# ULED.net
KiCad netlist of a schematic drawn in Altium Designer
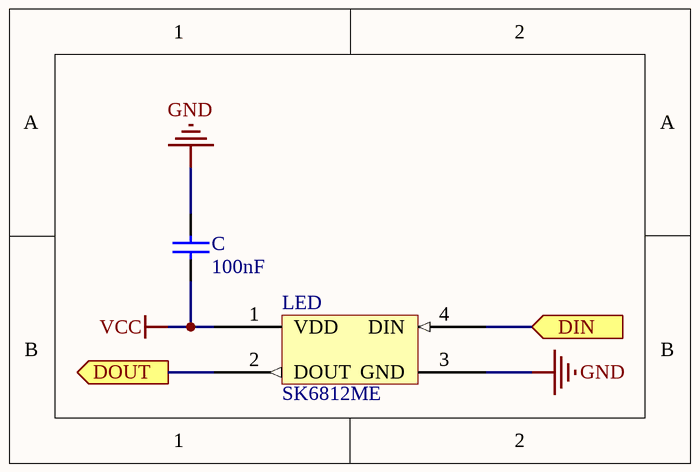
[diagram p0: ULED.SchDoc]

(export (version "E")
  (design (tool "Eeschema 10.0.6"))
  (components
    (comp (ref "C")
      (value "100nF")
      (footprint "CAPC1005X55X30LL05T10")
      (fields (field (name "MANUFACTURER") "Kemet") (field (name "PART NUMBER") "C0402C104K4RACTU"))
      (libsource (lib "Altium Content Vault") (part "CAP"))
    )
    (comp (ref "LED")
      (value "SK6812ME")
      (footprint "SK6812ME")
      (description "Individually Adressable SK6812 Mini-E 3528 LED")
      (libsource (lib "Skayboard") (part "SK6812"))
    )
  )
  (nets
    (net (code "1") (name "/DIN") (class "Default")
      (node (ref "LED") (pin "4") (pinfunction "DIN_4") (pintype "input"))
    )
    (net (code "2") (name "/DOUT") (class "Default")
      (node (ref "LED") (pin "2") (pinfunction "DOUT_2") (pintype "output"))
    )
    (net (code "3") (name "GND") (class "Default")
      (node (ref "C") (pin "2") (pinfunction "2_2") (pintype "passive"))
      (node (ref "LED") (pin "3") (pinfunction "GND_3") (pintype "power_in"))
    )
    (net (code "4") (name "VCC") (class "Default")
      (node (ref "C") (pin "1") (pinfunction "1_1") (pintype "passive"))
      (node (ref "LED") (pin "1") (pinfunction "VDD_1") (pintype "power_in"))
    )
  )
)
